# Water_Use_Monitor.net
KiCad netlist of a schematic drawn in EAGLE
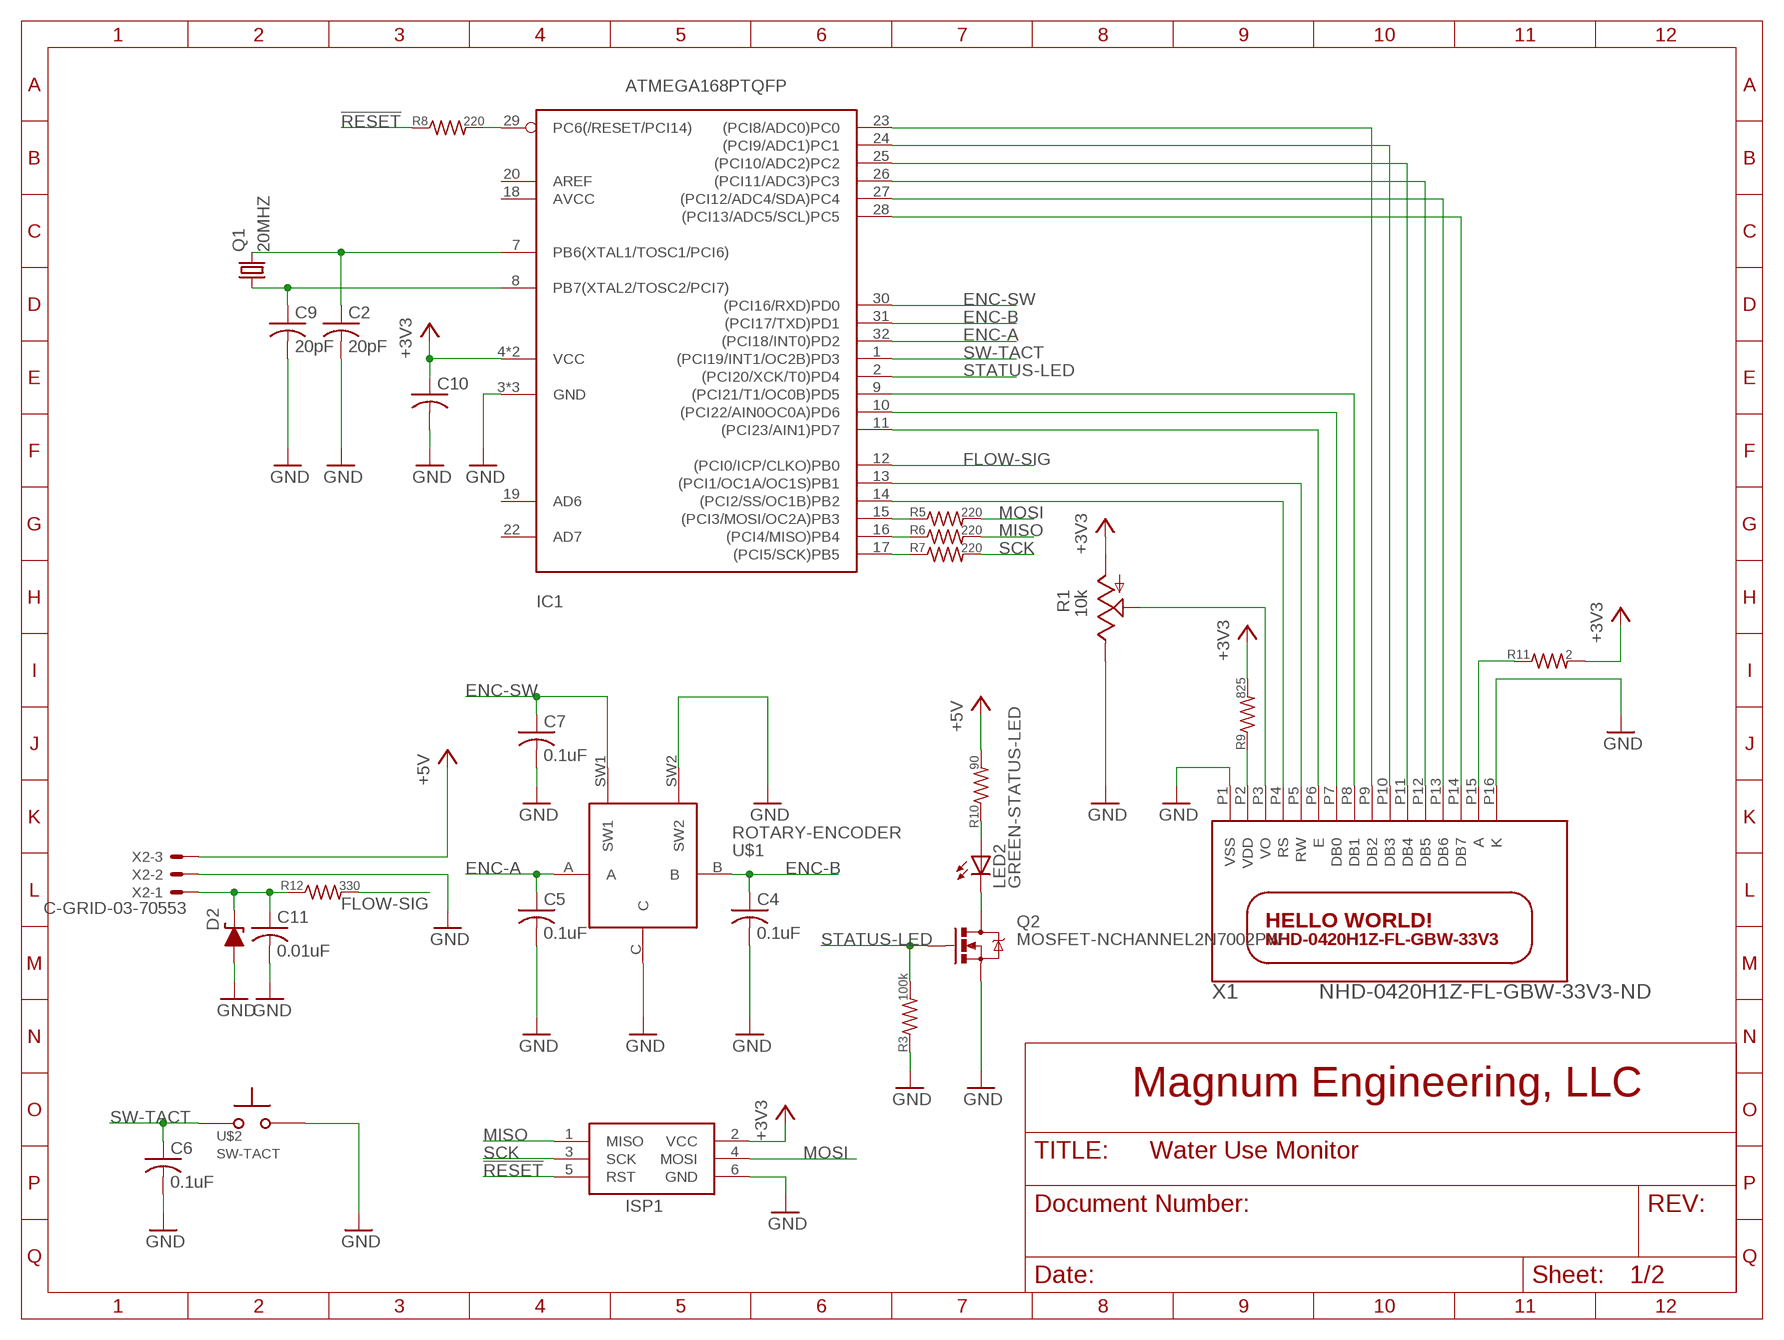
[diagram p0: schematic, sheet 1]
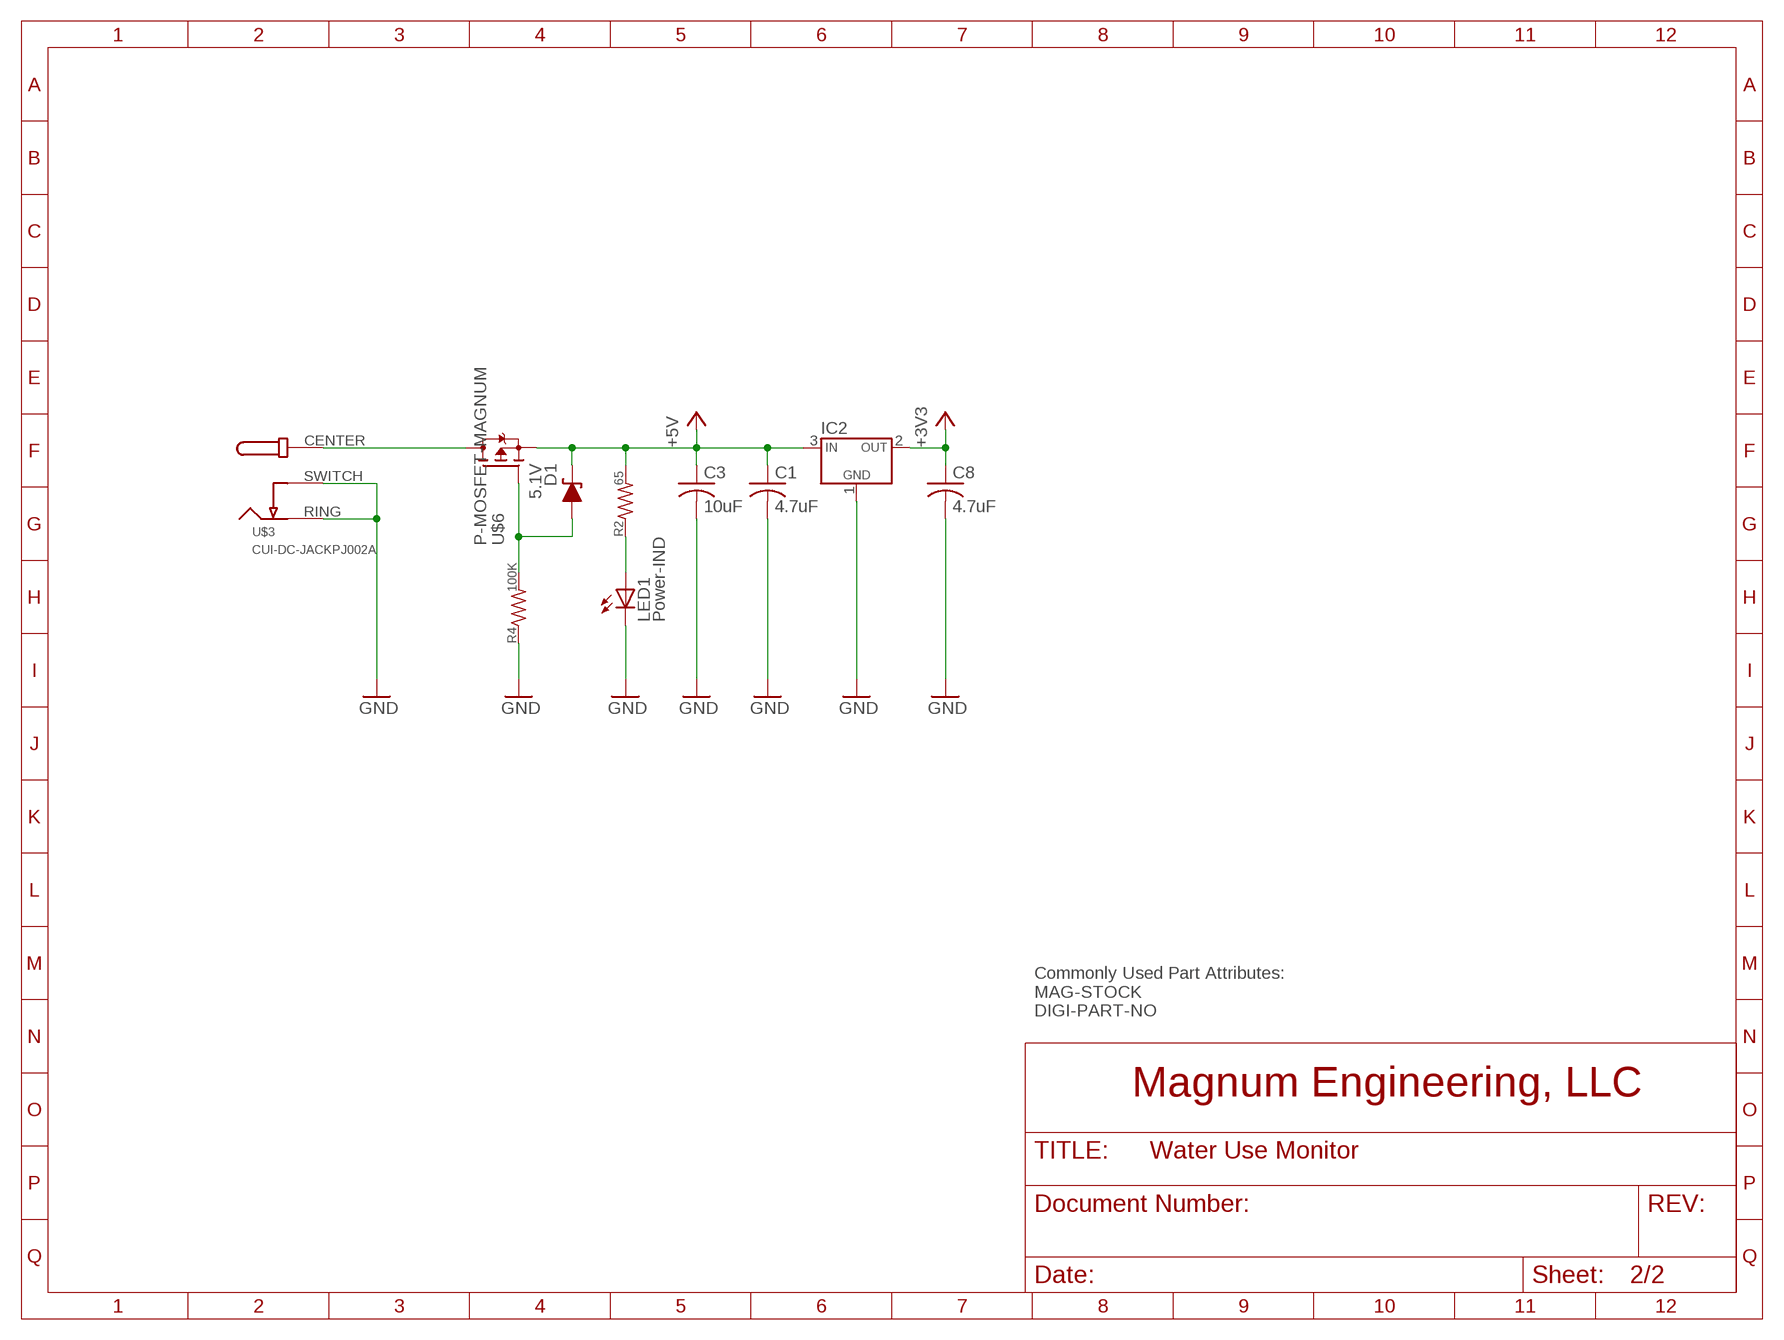
[diagram p1: schematic, sheet 2]

(export (version "E")
  (design (tool "Eeschema 10.0.6"))
  (components
    (comp (ref "C1")
      (value "4.7uF")
      (footprint "eagle-import:C0805")
      (libsource (lib "eagle-import") (part "CAPACITOR0805"))
    )
    (comp (ref "C3")
      (value "10uF")
      (footprint "eagle-import:C0805")
      (libsource (lib "eagle-import") (part "CAPACITOR0805"))
    )
    (comp (ref "C8")
      (value "4.7uF")
      (footprint "eagle-import:C0805")
      (libsource (lib "eagle-import") (part "CAPACITOR0805"))
    )
    (comp (ref "D1")
      (value "5.1V")
      (footprint "eagle-import:SOT-23")
      (libsource (lib "eagle-import") (part "ZENERSOT-23"))
    )
    (comp (ref "IC2")
      (value "VREGLD1117-XX")
      (footprint "eagle-import:DPAK")
      (libsource (lib "eagle-import") (part "VREGLD1117-XX"))
    )
    (comp (ref "LED1")
      (value "Power-IND")
      (footprint "eagle-import:LED5MM")
      (libsource (lib "eagle-import") (part "LED5MM"))
    )
    (comp (ref "R2")
      (value "65")
      (footprint "eagle-import:R0805")
      (libsource (lib "eagle-import") (part "RESISTOR0805"))
    )
    (comp (ref "R4")
      (value "100K")
      (footprint "eagle-import:R0805")
      (libsource (lib "eagle-import") (part "RESISTOR0805"))
    )
    (comp (ref "U$3")
      (value "CUI-DC-JACKPJ002A")
      (footprint "eagle-import:PJ002A")
      (libsource (lib "eagle-import") (part "CUI-DC-JACKPJ002A"))
    )
    (comp (ref "U$6")
      (value "P-MOSFET-MAGNUM")
      (footprint "eagle-import:SOT23")
      (libsource (lib "eagle-import") (part "P-MOSFET-MAGNUM"))
    )
    (comp (ref "C2")
      (value "20pF")
      (footprint "eagle-import:C0805")
      (libsource (lib "eagle-import") (part "CAPACITOR0805"))
    )
    (comp (ref "C4")
      (value "0.1uF")
      (footprint "eagle-import:C0805")
      (libsource (lib "eagle-import") (part "CAPACITOR0805"))
    )
    (comp (ref "C5")
      (value "0.1uF")
      (footprint "eagle-import:C0805")
      (libsource (lib "eagle-import") (part "CAPACITOR0805"))
    )
    (comp (ref "C6")
      (value "0.1uF")
      (footprint "eagle-import:C0805")
      (libsource (lib "eagle-import") (part "CAPACITOR0805"))
    )
    (comp (ref "C7")
      (value "0.1uF")
      (footprint "eagle-import:C0805")
      (libsource (lib "eagle-import") (part "CAPACITOR0805"))
    )
    (comp (ref "C9")
      (value "20pF")
      (footprint "eagle-import:C0805")
      (libsource (lib "eagle-import") (part "CAPACITOR0805"))
    )
    (comp (ref "C10")
      (value "CAPACITOR0805")
      (footprint "eagle-import:C0805")
      (libsource (lib "eagle-import") (part "CAPACITOR0805"))
    )
    (comp (ref "C11")
      (value "0.01uF")
      (footprint "eagle-import:C0805")
      (libsource (lib "eagle-import") (part "CAPACITOR0805"))
    )
    (comp (ref "D2")
      (value "ZENERSOD-123")
      (footprint "eagle-import:SOD-123")
      (libsource (lib "eagle-import") (part "ZENERSOD-123"))
    )
    (comp (ref "IC1")
      (value "ATMEGA168PTQFP")
      (footprint "eagle-import:ADS4_TQFP32-08")
      (libsource (lib "eagle-import") (part "ATMEGA168PTQFP"))
    )
    (comp (ref "ISP1")
      (value "AVRISP-6")
      (footprint "eagle-import:AVRISP")
      (libsource (lib "eagle-import") (part "AVRISP-6"))
    )
    (comp (ref "LED2")
      (value "GREEN-STATUS-LED")
      (footprint "eagle-import:LED5MM")
      (libsource (lib "eagle-import") (part "LED5MM"))
    )
    (comp (ref "Q1")
      (value "20MHZ")
      (footprint "eagle-import:20MHZ")
      (libsource (lib "eagle-import") (part "CRYSTAL"))
    )
    (comp (ref "Q2")
      (value "MOSFET-NCHANNEL2N7002PW")
      (footprint "eagle-import:SOT323")
      (libsource (lib "eagle-import") (part "MOSFET-NCHANNEL2N7002PW"))
    )
    (comp (ref "R1")
      (value "10k")
      (footprint "eagle-import:POT_RS3")
      (libsource (lib "eagle-import") (part "POTENTIOMETER"))
    )
    (comp (ref "R3")
      (value "100k")
      (footprint "eagle-import:R0805")
      (libsource (lib "eagle-import") (part "RESISTOR0805"))
    )
    (comp (ref "R5")
      (value "220")
      (footprint "eagle-import:R0805")
      (libsource (lib "eagle-import") (part "RESISTOR0805"))
    )
    (comp (ref "R6")
      (value "220")
      (footprint "eagle-import:R0805")
      (libsource (lib "eagle-import") (part "RESISTOR0805"))
    )
    (comp (ref "R7")
      (value "220")
      (footprint "eagle-import:R0805")
      (libsource (lib "eagle-import") (part "RESISTOR0805"))
    )
    (comp (ref "R8")
      (value "220")
      (footprint "eagle-import:R0805")
      (libsource (lib "eagle-import") (part "RESISTOR0805"))
    )
    (comp (ref "R9")
      (value "825")
      (footprint "eagle-import:R0805")
      (libsource (lib "eagle-import") (part "RESISTOR0805"))
    )
    (comp (ref "R10")
      (value "90")
      (footprint "eagle-import:R0805")
      (libsource (lib "eagle-import") (part "RESISTOR0805"))
    )
    (comp (ref "R11")
      (value "2")
      (footprint "eagle-import:R0805")
      (libsource (lib "eagle-import") (part "RESISTOR0805"))
    )
    (comp (ref "R12")
      (value "330")
      (footprint "eagle-import:R0805")
      (libsource (lib "eagle-import") (part "RESISTOR0805"))
    )
    (comp (ref "U$1")
      (value "ROTARY-ENCODER")
      (footprint "eagle-import:ROTARY-ENCODER")
      (libsource (lib "eagle-import") (part "ROTARY-ENCODER"))
    )
    (comp (ref "U$2")
      (value "SW-TACT")
      (footprint "eagle-import:FSM15JLH")
      (libsource (lib "eagle-import") (part "SW-TACT"))
    )
    (comp (ref "X1")
      (value "NHD-0420H1Z-FL-GBW-33V3-ND")
      (footprint "eagle-import:NEWHAVEN-LCD")
      (libsource (lib "eagle-import") (part "HD44780LCD"))
    )
    (comp (ref "X2")
      (value "C-GRID-03-70553")
      (footprint "eagle-import:70553-03")
      (libsource (lib "eagle-import") (part "C-GRID-03-70553"))
    )
  )
  (nets
    (net (code "1") (name "+3V3") (class "Default")
      (node (ref "C10") (pin "1") (pinfunction "1_1") (pintype "passive"))
      (node (ref "C8") (pin "1") (pinfunction "1_1") (pintype "passive"))
      (node (ref "IC1") (pin "4") (pinfunction "VCC_4") (pintype "bidirectional"))
      (node (ref "IC1") (pin "6") (pinfunction "VCC_6") (pintype "bidirectional"))
      (node (ref "IC2") (pin "2") (pinfunction "OUT_2") (pintype "passive"))
      (node (ref "ISP1") (pin "2") (pinfunction "VCC_2") (pintype "power_in"))
      (node (ref "R1") (pin "A") (pinfunction "A_A") (pintype "passive"))
      (node (ref "R11") (pin "2") (pinfunction "2_2") (pintype "passive"))
      (node (ref "R9") (pin "2") (pinfunction "2_2") (pintype "passive"))
    )
    (net (code "2") (name "+5V") (class "Default")
      (node (ref "C1") (pin "1") (pinfunction "1_1") (pintype "passive"))
      (node (ref "C3") (pin "1") (pinfunction "1_1") (pintype "passive"))
      (node (ref "D1") (pin "3") (pinfunction "K_3") (pintype "passive"))
      (node (ref "IC2") (pin "3") (pinfunction "IN_3") (pintype "passive"))
      (node (ref "R10") (pin "2") (pinfunction "2_2") (pintype "passive"))
      (node (ref "R2") (pin "2") (pinfunction "2_2") (pintype "passive"))
      (node (ref "U$6") (pin "2") (pinfunction "S_2") (pintype "passive"))
      (node (ref "X2") (pin "3") (pinfunction "S_3") (pintype "passive"))
    )
    (net (code "3") (name "ENC-A") (class "Default")
      (node (ref "C5") (pin "1") (pinfunction "1_1") (pintype "passive"))
      (node (ref "IC1") (pin "32") (pinfunction "(PCI18/INT0)PD2_32") (pintype "bidirectional"))
      (node (ref "U$1") (pin "A") (pinfunction "A_A") (pintype "bidirectional"))
    )
    (net (code "4") (name "ENC-B") (class "Default")
      (node (ref "C4") (pin "1") (pinfunction "1_1") (pintype "passive"))
      (node (ref "IC1") (pin "31") (pinfunction "(PCI17/TXD)PD1_31") (pintype "bidirectional"))
      (node (ref "U$1") (pin "B") (pinfunction "B_B") (pintype "bidirectional"))
    )
    (net (code "5") (name "ENC-SW") (class "Default")
      (node (ref "C7") (pin "1") (pinfunction "1_1") (pintype "passive"))
      (node (ref "IC1") (pin "30") (pinfunction "(PCI16/RXD)PD0_30") (pintype "bidirectional"))
      (node (ref "U$1") (pin "SW1") (pinfunction "SW1_SW1") (pintype "bidirectional"))
    )
    (net (code "6") (name "FLOW-SIG") (class "Default")
      (node (ref "IC1") (pin "12") (pinfunction "(PCI0/ICP/CLKO)PB0_12") (pintype "bidirectional"))
      (node (ref "R12") (pin "2") (pinfunction "2_2") (pintype "passive"))
    )
    (net (code "7") (name "GND") (class "Default")
      (node (ref "C1") (pin "2") (pinfunction "2_2") (pintype "passive"))
      (node (ref "C10") (pin "2") (pinfunction "2_2") (pintype "passive"))
      (node (ref "C11") (pin "2") (pinfunction "2_2") (pintype "passive"))
      (node (ref "C2") (pin "2") (pinfunction "2_2") (pintype "passive"))
      (node (ref "C3") (pin "2") (pinfunction "2_2") (pintype "passive"))
      (node (ref "C4") (pin "2") (pinfunction "2_2") (pintype "passive"))
      (node (ref "C5") (pin "2") (pinfunction "2_2") (pintype "passive"))
      (node (ref "C6") (pin "2") (pinfunction "2_2") (pintype "passive"))
      (node (ref "C7") (pin "2") (pinfunction "2_2") (pintype "passive"))
      (node (ref "C8") (pin "2") (pinfunction "2_2") (pintype "passive"))
      (node (ref "C9") (pin "2") (pinfunction "2_2") (pintype "passive"))
      (node (ref "D2") (pin "A") (pinfunction "A_A") (pintype "passive"))
      (node (ref "IC1") (pin "21") (pinfunction "GND_21") (pintype "bidirectional"))
      (node (ref "IC1") (pin "3") (pinfunction "GND_3") (pintype "bidirectional"))
      (node (ref "IC1") (pin "5") (pinfunction "GND_5") (pintype "bidirectional"))
      (node (ref "IC2") (pin "1") (pinfunction "GND_1") (pintype "passive"))
      (node (ref "ISP1") (pin "6") (pinfunction "GND_6") (pintype "power_in"))
      (node (ref "LED1") (pin "K") (pinfunction "C_K") (pintype "passive"))
      (node (ref "Q2") (pin "2") (pinfunction "S_2") (pintype "passive"))
      (node (ref "R1") (pin "E") (pinfunction "E_E") (pintype "passive"))
      (node (ref "R3") (pin "1") (pinfunction "1_1") (pintype "passive"))
      (node (ref "R4") (pin "1") (pinfunction "1_1") (pintype "passive"))
      (node (ref "U$1") (pin "C") (pinfunction "C_C") (pintype "bidirectional"))
      (node (ref "U$1") (pin "SW2") (pinfunction "SW2_SW2") (pintype "bidirectional"))
      (node (ref "U$2") (pin "P$3") (pinfunction "P$2_P$3") (pintype "bidirectional"))
      (node (ref "U$2") (pin "P$4") (pinfunction "P$2_P$4") (pintype "bidirectional"))
      (node (ref "U$3") (pin "RING") (pinfunction "RING_RING") (pintype "bidirectional"))
      (node (ref "U$3") (pin "SWITCH") (pinfunction "SW_SWITCH") (pintype "bidirectional"))
      (node (ref "X1") (pin "P1") (pinfunction "VSS_P1") (pintype "power_in"))
      (node (ref "X1") (pin "P16") (pinfunction "K_P16") (pintype "input"))
      (node (ref "X2") (pin "2") (pinfunction "S_2") (pintype "passive"))
    )
    (net (code "8") (name "MISO") (class "Default")
      (node (ref "ISP1") (pin "1") (pinfunction "MISO_1") (pintype "input"))
      (node (ref "R6") (pin "2") (pinfunction "2_2") (pintype "passive"))
    )
    (net (code "9") (name "MOSI") (class "Default")
      (node (ref "ISP1") (pin "4") (pinfunction "MOSI_4") (pintype "output"))
      (node (ref "R5") (pin "2") (pinfunction "2_2") (pintype "passive"))
    )
    (net (code "10") (name "Net-(D1-A)") (class "Default")
      (node (ref "D1") (pin "1") (pinfunction "A_1") (pintype "passive"))
      (node (ref "R4") (pin "2") (pinfunction "2_2") (pintype "passive"))
      (node (ref "U$6") (pin "1") (pinfunction "G_1") (pintype "passive"))
    )
    (net (code "11") (name "Net-(IC1-(PCI1{slash}OC1A{slash}OC1S)PB1)") (class "Default")
      (node (ref "IC1") (pin "13") (pinfunction "(PCI1/OC1A/OC1S)PB1_13") (pintype "bidirectional"))
      (node (ref "X1") (pin "P5") (pinfunction "RW_P5") (pintype "input"))
    )
    (net (code "12") (name "Net-(IC1-(PCI2{slash}SS{slash}OC1B)PB2)") (class "Default")
      (node (ref "IC1") (pin "14") (pinfunction "(PCI2/SS/OC1B)PB2_14") (pintype "bidirectional"))
      (node (ref "X1") (pin "P4") (pinfunction "RS_P4") (pintype "input"))
    )
    (net (code "13") (name "Net-(IC1-(PCI3{slash}MOSI{slash}OC2A)PB3)") (class "Default")
      (node (ref "IC1") (pin "15") (pinfunction "(PCI3/MOSI/OC2A)PB3_15") (pintype "bidirectional"))
      (node (ref "R5") (pin "1") (pinfunction "1_1") (pintype "passive"))
    )
    (net (code "14") (name "Net-(IC1-(PCI4{slash}MISO)PB4)") (class "Default")
      (node (ref "IC1") (pin "16") (pinfunction "(PCI4/MISO)PB4_16") (pintype "bidirectional"))
      (node (ref "R6") (pin "1") (pinfunction "1_1") (pintype "passive"))
    )
    (net (code "15") (name "Net-(IC1-(PCI5{slash}SCK)PB5)") (class "Default")
      (node (ref "IC1") (pin "17") (pinfunction "(PCI5/SCK)PB5_17") (pintype "bidirectional"))
      (node (ref "R7") (pin "1") (pinfunction "1_1") (pintype "passive"))
    )
    (net (code "16") (name "Net-(IC1-(PCI8{slash}ADC0)PC0)") (class "Default")
      (node (ref "IC1") (pin "23") (pinfunction "(PCI8/ADC0)PC0_23") (pintype "bidirectional"))
      (node (ref "X1") (pin "P9") (pinfunction "DB2_P9") (pintype "bidirectional"))
    )
    (net (code "17") (name "Net-(IC1-(PCI9{slash}ADC1)PC1)") (class "Default")
      (node (ref "IC1") (pin "24") (pinfunction "(PCI9/ADC1)PC1_24") (pintype "bidirectional"))
      (node (ref "X1") (pin "P10") (pinfunction "DB3_P10") (pintype "bidirectional"))
    )
    (net (code "18") (name "Net-(IC1-(PCI10{slash}ADC2)PC2)") (class "Default")
      (node (ref "IC1") (pin "25") (pinfunction "(PCI10/ADC2)PC2_25") (pintype "bidirectional"))
      (node (ref "X1") (pin "P11") (pinfunction "DB4_P11") (pintype "bidirectional"))
    )
    (net (code "19") (name "Net-(IC1-(PCI11{slash}ADC3)PC3)") (class "Default")
      (node (ref "IC1") (pin "26") (pinfunction "(PCI11/ADC3)PC3_26") (pintype "bidirectional"))
      (node (ref "X1") (pin "P12") (pinfunction "DB5_P12") (pintype "bidirectional"))
    )
    (net (code "20") (name "Net-(IC1-(PCI12{slash}ADC4{slash}SDA)PC4)") (class "Default")
      (node (ref "IC1") (pin "27") (pinfunction "(PCI12/ADC4/SDA)PC4_27") (pintype "bidirectional"))
      (node (ref "X1") (pin "P13") (pinfunction "DB6_P13") (pintype "bidirectional"))
    )
    (net (code "21") (name "Net-(IC1-(PCI13{slash}ADC5{slash}SCL)PC5)") (class "Default")
      (node (ref "IC1") (pin "28") (pinfunction "(PCI13/ADC5/SCL)PC5_28") (pintype "bidirectional"))
      (node (ref "X1") (pin "P14") (pinfunction "DB7_P14") (pintype "bidirectional"))
    )
    (net (code "22") (name "Net-(IC1-(PCI21{slash}T1{slash}OC0B)PD5)") (class "Default")
      (node (ref "IC1") (pin "9") (pinfunction "(PCI21/T1/OC0B)PD5_9") (pintype "bidirectional"))
      (node (ref "X1") (pin "P8") (pinfunction "DB1_P8") (pintype "bidirectional"))
    )
    (net (code "23") (name "Net-(IC1-(PCI22{slash}AIN0OC0A)PD6)") (class "Default")
      (node (ref "IC1") (pin "10") (pinfunction "(PCI22/AIN0OC0A)PD6_10") (pintype "bidirectional"))
      (node (ref "X1") (pin "P7") (pinfunction "DB0_P7") (pintype "bidirectional"))
    )
    (net (code "24") (name "Net-(IC1-(PCI23{slash}AIN1)PD7)") (class "Default")
      (node (ref "IC1") (pin "11") (pinfunction "(PCI23/AIN1)PD7_11") (pintype "bidirectional"))
      (node (ref "X1") (pin "P6") (pinfunction "E_P6") (pintype "input"))
    )
    (net (code "25") (name "Net-(IC1-PB6(XTAL1{slash}TOSC1{slash}PCI6))") (class "Default")
      (node (ref "C2") (pin "1") (pinfunction "1_1") (pintype "passive"))
      (node (ref "IC1") (pin "7") (pinfunction "PB6(XTAL1/TOSC1/PCI6)_7") (pintype "bidirectional"))
      (node (ref "Q1") (pin "P$2") (pinfunction "2_P$2") (pintype "passive"))
    )
    (net (code "26") (name "Net-(IC1-PB7(XTAL2{slash}TOSC2{slash}PCI7))") (class "Default")
      (node (ref "C9") (pin "1") (pinfunction "1_1") (pintype "passive"))
      (node (ref "IC1") (pin "8") (pinfunction "PB7(XTAL2/TOSC2/PCI7)_8") (pintype "bidirectional"))
      (node (ref "Q1") (pin "P$1") (pinfunction "1_P$1") (pintype "passive"))
    )
    (net (code "27") (name "Net-(IC1-PC6({slash}RESET{slash}PCI14))") (class "Default")
      (node (ref "IC1") (pin "29") (pinfunction "PC6(/RESET/PCI14)_29") (pintype "bidirectional"))
      (node (ref "R8") (pin "2") (pinfunction "2_2") (pintype "passive"))
    )
    (net (code "28") (name "Net-(LED1-PadA)") (class "Default")
      (node (ref "LED1") (pin "A") (pinfunction "A_A") (pintype "passive"))
      (node (ref "R2") (pin "1") (pinfunction "1_1") (pintype "passive"))
    )
    (net (code "29") (name "Net-(LED2-C)") (class "Default")
      (node (ref "LED2") (pin "K") (pinfunction "C_K") (pintype "passive"))
      (node (ref "Q2") (pin "3") (pinfunction "D_3") (pintype "passive"))
    )
    (net (code "30") (name "Net-(LED2-PadA)") (class "Default")
      (node (ref "LED2") (pin "A") (pinfunction "A_A") (pintype "passive"))
      (node (ref "R10") (pin "1") (pinfunction "1_1") (pintype "passive"))
    )
    (net (code "31") (name "Net-(U$6-D)") (class "Default")
      (node (ref "U$3") (pin "CENTER") (pinfunction "CENTER_CENTER") (pintype "bidirectional"))
      (node (ref "U$6") (pin "3") (pinfunction "D_3") (pintype "passive"))
    )
    (net (code "32") (name "Net-(X1-A)") (class "Default")
      (node (ref "R11") (pin "1") (pinfunction "1_1") (pintype "passive"))
      (node (ref "X1") (pin "P15") (pinfunction "A_P15") (pintype "input"))
    )
    (net (code "33") (name "Net-(X1-VDD)") (class "Default")
      (node (ref "R9") (pin "1") (pinfunction "1_1") (pintype "passive"))
      (node (ref "X1") (pin "P2") (pinfunction "VDD_P2") (pintype "power_in"))
    )
    (net (code "34") (name "Net-(X1-VO)") (class "Default")
      (node (ref "R1") (pin "S") (pinfunction "S_S") (pintype "passive"))
      (node (ref "X1") (pin "P3") (pinfunction "VO_P3") (pintype "input"))
    )
    (net (code "35") (name "Net-(X2A-S)") (class "Default")
      (node (ref "C11") (pin "1") (pinfunction "1_1") (pintype "passive"))
      (node (ref "D2") (pin "K") (pinfunction "K_K") (pintype "passive"))
      (node (ref "R12") (pin "1") (pinfunction "1_1") (pintype "passive"))
      (node (ref "X2") (pin "1") (pinfunction "S_1") (pintype "passive"))
    )
    (net (code "36") (name "SCK") (class "Default")
      (node (ref "ISP1") (pin "3") (pinfunction "SCK_3") (pintype "output"))
      (node (ref "R7") (pin "2") (pinfunction "2_2") (pintype "passive"))
    )
    (net (code "37") (name "STATUS-LED") (class "Default")
      (node (ref "IC1") (pin "2") (pinfunction "(PCI20/XCK/T0)PD4_2") (pintype "bidirectional"))
      (node (ref "Q2") (pin "1") (pinfunction "G_1") (pintype "passive"))
      (node (ref "R3") (pin "2") (pinfunction "2_2") (pintype "passive"))
    )
    (net (code "38") (name "SW-TACT") (class "Default")
      (node (ref "C6") (pin "1") (pinfunction "1_1") (pintype "passive"))
      (node (ref "IC1") (pin "1") (pinfunction "(PCI19/INT1/OC2B)PD3_1") (pintype "bidirectional"))
      (node (ref "U$2") (pin "P$1") (pinfunction "P$1_P$1") (pintype "bidirectional"))
      (node (ref "U$2") (pin "P$2") (pinfunction "P$1_P$2") (pintype "bidirectional"))
    )
    (net (code "39") (name "unconnected-(IC1-AD6-Pad19)") (class "Default")
      (node (ref "IC1") (pin "19") (pinfunction "AD6_19") (pintype "bidirectional"))
    )
    (net (code "40") (name "unconnected-(IC1-AD7-Pad22)") (class "Default")
      (node (ref "IC1") (pin "22") (pinfunction "AD7_22") (pintype "bidirectional"))
    )
    (net (code "41") (name "unconnected-(IC1-AREF-Pad20)") (class "Default")
      (node (ref "IC1") (pin "20") (pinfunction "AREF_20") (pintype "bidirectional"))
    )
    (net (code "42") (name "unconnected-(IC1-AVCC-Pad18)") (class "Default")
      (node (ref "IC1") (pin "18") (pinfunction "AVCC_18") (pintype "bidirectional"))
    )
    (net (code "43") (name "~{RESET}") (class "Default")
      (node (ref "ISP1") (pin "5") (pinfunction "RST_5") (pintype "output"))
      (node (ref "R8") (pin "1") (pinfunction "1_1") (pintype "passive"))
    )
  )
)
